# Power.net
KiCad netlist of a schematic drawn in Altium Designer
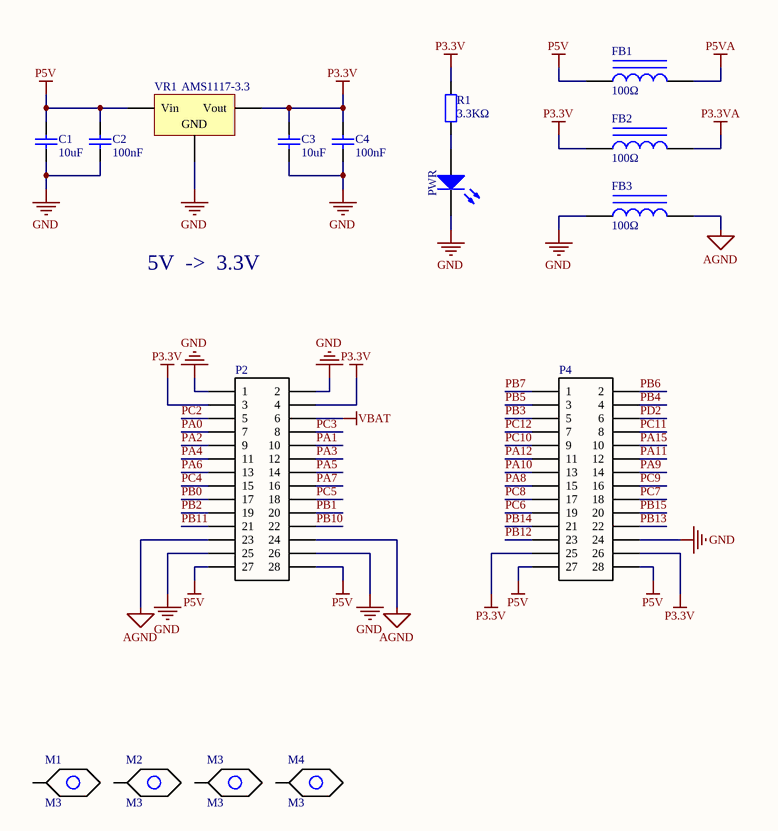
[diagram p0: Power.SchDoc]

(export (version "E")
  (design (tool "Eeschema 10.0.6"))
  (components
    (comp (ref "C1")
      (value "10uF")
      (footprint "0603_C")
      (description "贴片电容")
      (libsource (lib "Miscellaneous Devices LC") (part "0603 10uF (106) 10% 10V"))
    )
    (comp (ref "C2")
      (value "100nF")
      (footprint "0402_C")
      (description "贴片电容")
      (libsource (lib "Miscellaneous Devices LC") (part "0402 100nF (104) 10% 16V"))
    )
    (comp (ref "C3")
      (value "10uF")
      (footprint "0603_C")
      (description "贴片电容")
      (libsource (lib "Miscellaneous Devices LC") (part "0603 10uF (106) 10% 10V"))
    )
    (comp (ref "C4")
      (value "100nF")
      (footprint "0402_C")
      (description "贴片电容")
      (libsource (lib "Miscellaneous Devices LC") (part "0402 100nF (104) 10% 16V"))
    )
    (comp (ref "FB1")
      (value "100Ω")
      (footprint "0805_L")
      (description "贴片磁珠")
      (libsource (lib "Miscellaneous Devices LC") (part "0805 100Ω 25% 100MHz"))
    )
    (comp (ref "FB2")
      (value "100Ω")
      (footprint "0805_L")
      (description "贴片磁珠")
      (libsource (lib "Miscellaneous Devices LC") (part "0805 100Ω 25% 100MHz"))
    )
    (comp (ref "FB3")
      (value "100Ω")
      (footprint "0805_L")
      (description "贴片磁珠")
      (libsource (lib "Miscellaneous Devices LC") (part "0805 100Ω 25% 100MHz"))
    )
    (comp (ref "M1") (value "M3") (footprint "M3") (libsource (lib "Connectors") (part "M3")))
    (comp (ref "M2") (value "M3") (footprint "M3") (libsource (lib "Connectors") (part "M3")))
    (comp (ref "M3") (value "M3") (footprint "M3") (libsource (lib "Connectors") (part "M3")))
    (comp (ref "M4") (value "M3") (footprint "M3") (libsource (lib "Connectors") (part "M3")))
    (comp (ref "P2")
      (value "Header 14X2")
      (footprint "DIP28-2.54")
      (description "Header, 14-Pin, Dual row")
      (fields (field (name "PUBLISHER") "Altium Limited"))
      (libsource (lib "Connectors") (part "Header 14X2"))
    )
    (comp (ref "P4")
      (value "Header 14X2")
      (footprint "DIP28-2.54")
      (description "Header, 14-Pin, Dual row")
      (fields (field (name "PUBLISHER") "Altium Limited"))
      (libsource (lib "Connectors") (part "Header 14X2"))
    )
    (comp (ref "PWR")
      (value "蓝灯 0603")
      (footprint "0603_LED_S1")
      (description "发光二极管")
      (libsource (lib "Miscellaneous Devices LC") (part "0603 蓝灯"))
    )
    (comp (ref "R1")
      (value "3.3KΩ")
      (footprint "0402_R")
      (description "贴片电阻")
      (libsource (lib "Miscellaneous Devices LC") (part "0402 3.3KΩ (3301) 1%"))
    )
    (comp (ref "VR1")
      (value "AMS1117-3.3")
      (footprint "SOT-223")
      (description "低压差线性稳压(LDO)")
      (libsource (lib "Miscellaneous Devices LC") (part "SOT-223 AMS1117-3.3"))
    )
  )
  (nets
    (net (code "1") (name "/PA0") (class "Default")
      (node (ref "P2") (pin "7") (pinfunction "7_7") (pintype "passive"))
    )
    (net (code "2") (name "/PA1") (class "Default")
      (node (ref "P2") (pin "10") (pinfunction "10_10") (pintype "passive"))
    )
    (net (code "3") (name "/PA2") (class "Default")
      (node (ref "P2") (pin "9") (pinfunction "9_9") (pintype "passive"))
    )
    (net (code "4") (name "/PA3") (class "Default")
      (node (ref "P2") (pin "12") (pinfunction "12_12") (pintype "passive"))
    )
    (net (code "5") (name "/PA4") (class "Default")
      (node (ref "P2") (pin "11") (pinfunction "11_11") (pintype "passive"))
    )
    (net (code "6") (name "/PA5") (class "Default")
      (node (ref "P2") (pin "14") (pinfunction "14_14") (pintype "passive"))
    )
    (net (code "7") (name "/PA6") (class "Default")
      (node (ref "P2") (pin "13") (pinfunction "13_13") (pintype "passive"))
    )
    (net (code "8") (name "/PA7") (class "Default")
      (node (ref "P2") (pin "16") (pinfunction "16_16") (pintype "passive"))
    )
    (net (code "9") (name "/PA8") (class "Default")
      (node (ref "P4") (pin "15") (pinfunction "15_15") (pintype "passive"))
    )
    (net (code "10") (name "/PA9") (class "Default")
      (node (ref "P4") (pin "14") (pinfunction "14_14") (pintype "passive"))
    )
    (net (code "11") (name "/PA10") (class "Default")
      (node (ref "P4") (pin "13") (pinfunction "13_13") (pintype "passive"))
    )
    (net (code "12") (name "/PA11") (class "Default")
      (node (ref "P4") (pin "12") (pinfunction "12_12") (pintype "passive"))
    )
    (net (code "13") (name "/PA12") (class "Default")
      (node (ref "P4") (pin "11") (pinfunction "11_11") (pintype "passive"))
    )
    (net (code "14") (name "/PA15") (class "Default")
      (node (ref "P4") (pin "10") (pinfunction "10_10") (pintype "passive"))
    )
    (net (code "15") (name "/PB0") (class "Default")
      (node (ref "P2") (pin "17") (pinfunction "17_17") (pintype "passive"))
    )
    (net (code "16") (name "/PB1") (class "Default")
      (node (ref "P2") (pin "20") (pinfunction "20_20") (pintype "passive"))
    )
    (net (code "17") (name "/PB2") (class "Default")
      (node (ref "P2") (pin "19") (pinfunction "19_19") (pintype "passive"))
    )
    (net (code "18") (name "/PB3") (class "Default")
      (node (ref "P4") (pin "5") (pinfunction "5_5") (pintype "passive"))
    )
    (net (code "19") (name "/PB4") (class "Default")
      (node (ref "P4") (pin "4") (pinfunction "4_4") (pintype "passive"))
    )
    (net (code "20") (name "/PB5") (class "Default")
      (node (ref "P4") (pin "3") (pinfunction "3_3") (pintype "passive"))
    )
    (net (code "21") (name "/PB6") (class "Default")
      (node (ref "P4") (pin "2") (pinfunction "2_2") (pintype "passive"))
    )
    (net (code "22") (name "/PB7") (class "Default")
      (node (ref "P4") (pin "1") (pinfunction "1_1") (pintype "passive"))
    )
    (net (code "23") (name "/PB10") (class "Default")
      (node (ref "P2") (pin "22") (pinfunction "22_22") (pintype "passive"))
    )
    (net (code "24") (name "/PB11") (class "Default")
      (node (ref "P2") (pin "21") (pinfunction "21_21") (pintype "passive"))
    )
    (net (code "25") (name "/PB12") (class "Default")
      (node (ref "P4") (pin "23") (pinfunction "23_23") (pintype "passive"))
    )
    (net (code "26") (name "/PB13") (class "Default")
      (node (ref "P4") (pin "22") (pinfunction "22_22") (pintype "passive"))
    )
    (net (code "27") (name "/PB14") (class "Default")
      (node (ref "P4") (pin "21") (pinfunction "21_21") (pintype "passive"))
    )
    (net (code "28") (name "/PB15") (class "Default")
      (node (ref "P4") (pin "20") (pinfunction "20_20") (pintype "passive"))
    )
    (net (code "29") (name "/PC2") (class "Default")
      (node (ref "P2") (pin "5") (pinfunction "5_5") (pintype "passive"))
    )
    (net (code "30") (name "/PC3") (class "Default")
      (node (ref "P2") (pin "8") (pinfunction "8_8") (pintype "passive"))
    )
    (net (code "31") (name "/PC4") (class "Default")
      (node (ref "P2") (pin "15") (pinfunction "15_15") (pintype "passive"))
    )
    (net (code "32") (name "/PC5") (class "Default")
      (node (ref "P2") (pin "18") (pinfunction "18_18") (pintype "passive"))
    )
    (net (code "33") (name "/PC6") (class "Default")
      (node (ref "P4") (pin "19") (pinfunction "19_19") (pintype "passive"))
    )
    (net (code "34") (name "/PC7") (class "Default")
      (node (ref "P4") (pin "18") (pinfunction "18_18") (pintype "passive"))
    )
    (net (code "35") (name "/PC8") (class "Default")
      (node (ref "P4") (pin "17") (pinfunction "17_17") (pintype "passive"))
    )
    (net (code "36") (name "/PC9") (class "Default")
      (node (ref "P4") (pin "16") (pinfunction "16_16") (pintype "passive"))
    )
    (net (code "37") (name "/PC10") (class "Default")
      (node (ref "P4") (pin "9") (pinfunction "9_9") (pintype "passive"))
    )
    (net (code "38") (name "/PC11") (class "Default")
      (node (ref "P4") (pin "8") (pinfunction "8_8") (pintype "passive"))
    )
    (net (code "39") (name "/PC12") (class "Default")
      (node (ref "P4") (pin "7") (pinfunction "7_7") (pintype "passive"))
    )
    (net (code "40") (name "/PD2") (class "Default")
      (node (ref "P4") (pin "6") (pinfunction "6_6") (pintype "passive"))
    )
    (net (code "41") (name "AGND") (class "Default")
      (node (ref "FB3") (pin "2") (pinfunction "2_2") (pintype "passive"))
      (node (ref "P2") (pin "23") (pinfunction "23_23") (pintype "passive"))
      (node (ref "P2") (pin "24") (pinfunction "24_24") (pintype "passive"))
    )
    (net (code "42") (name "GND") (class "Default")
      (node (ref "C1") (pin "1") (pinfunction "1_1") (pintype "passive"))
      (node (ref "C2") (pin "1") (pinfunction "1_1") (pintype "passive"))
      (node (ref "C3") (pin "1") (pinfunction "1_1") (pintype "passive"))
      (node (ref "C4") (pin "1") (pinfunction "1_1") (pintype "passive"))
      (node (ref "FB3") (pin "1") (pinfunction "1_1") (pintype "passive"))
      (node (ref "P2") (pin "1") (pinfunction "1_1") (pintype "passive"))
      (node (ref "P2") (pin "2") (pinfunction "2_2") (pintype "passive"))
      (node (ref "P2") (pin "25") (pinfunction "25_25") (pintype "passive"))
      (node (ref "P2") (pin "26") (pinfunction "26_26") (pintype "passive"))
      (node (ref "P4") (pin "24") (pinfunction "24_24") (pintype "passive"))
      (node (ref "PWR") (pin "K") (pinfunction "K_K") (pintype "passive"))
      (node (ref "VR1") (pin "1") (pinfunction "GND_1") (pintype "passive"))
    )
    (net (code "43") (name "Net-(PWR-PadA)") (class "Default")
      (node (ref "PWR") (pin "A") (pinfunction "A_A") (pintype "passive"))
      (node (ref "R1") (pin "1") (pinfunction "1_1") (pintype "passive"))
    )
    (net (code "44") (name "P3.3V") (class "Default")
      (node (ref "C3") (pin "2") (pinfunction "2_2") (pintype "passive"))
      (node (ref "C4") (pin "2") (pinfunction "2_2") (pintype "passive"))
      (node (ref "FB2") (pin "1") (pinfunction "1_1") (pintype "passive"))
      (node (ref "P2") (pin "3") (pinfunction "3_3") (pintype "passive"))
      (node (ref "P2") (pin "4") (pinfunction "4_4") (pintype "passive"))
      (node (ref "P4") (pin "25") (pinfunction "25_25") (pintype "passive"))
      (node (ref "P4") (pin "26") (pinfunction "26_26") (pintype "passive"))
      (node (ref "R1") (pin "2") (pinfunction "2_2") (pintype "passive"))
      (node (ref "VR1") (pin "2") (pinfunction "Vout_2") (pintype "passive"))
    )
    (net (code "45") (name "P3.3VA") (class "Default")
      (node (ref "FB2") (pin "2") (pinfunction "2_2") (pintype "passive"))
    )
    (net (code "46") (name "P5V") (class "Default")
      (node (ref "C1") (pin "2") (pinfunction "2_2") (pintype "passive"))
      (node (ref "C2") (pin "2") (pinfunction "2_2") (pintype "passive"))
      (node (ref "FB1") (pin "1") (pinfunction "1_1") (pintype "passive"))
      (node (ref "P2") (pin "27") (pinfunction "27_27") (pintype "passive"))
      (node (ref "P2") (pin "28") (pinfunction "28_28") (pintype "passive"))
      (node (ref "P4") (pin "27") (pinfunction "27_27") (pintype "passive"))
      (node (ref "P4") (pin "28") (pinfunction "28_28") (pintype "passive"))
      (node (ref "VR1") (pin "3") (pinfunction "Vin_3") (pintype "passive"))
    )
    (net (code "47") (name "P5VA") (class "Default")
      (node (ref "FB1") (pin "2") (pinfunction "2_2") (pintype "passive"))
    )
    (net (code "48") (name "VBAT") (class "Default")
      (node (ref "P2") (pin "6") (pinfunction "6_6") (pintype "passive"))
    )
    (net (code "49") (name "unconnected-(M1-Pad0)") (class "Default")
      (node (ref "M1") (pin "0") (pinfunction "0_0") (pintype "passive"))
    )
    (net (code "50") (name "unconnected-(M2-Pad0)") (class "Default")
      (node (ref "M2") (pin "0") (pinfunction "0_0") (pintype "passive"))
    )
    (net (code "51") (name "unconnected-(M3-Pad0)") (class "Default")
      (node (ref "M3") (pin "0") (pinfunction "0_0") (pintype "passive"))
    )
    (net (code "52") (name "unconnected-(M4-Pad0)") (class "Default")
      (node (ref "M4") (pin "0") (pinfunction "0_0") (pintype "passive"))
    )
  )
)
